# SparkBase.net
KiCad netlist of a schematic drawn in EAGLE
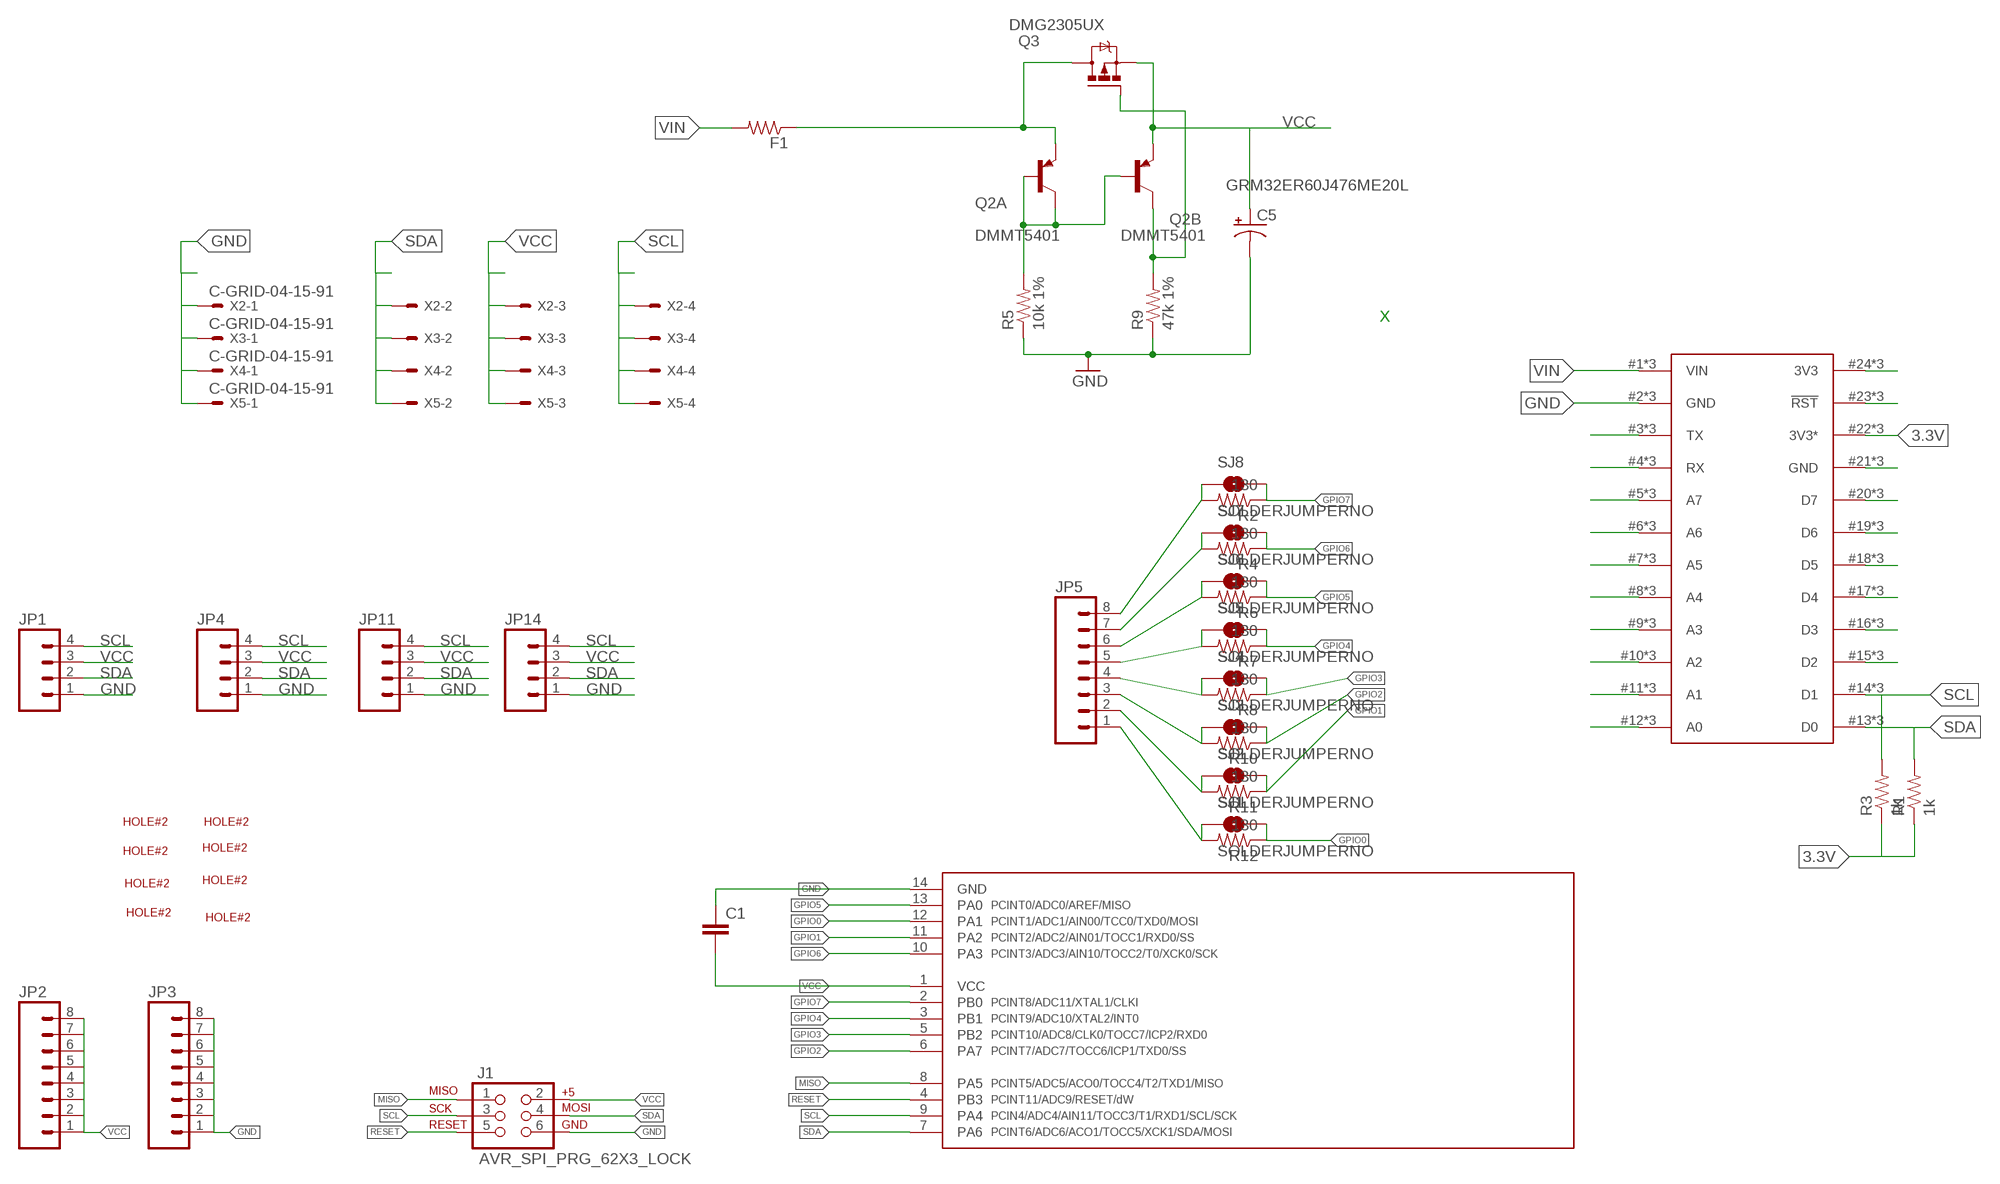
[diagram p0: schematic, sheet 1]

(export (version "E")
  (design (tool "Eeschema 10.0.6"))
  (components
    (comp (ref "C1")
      (value "CAP0805")
      (footprint "eagle-import:0805")
      (libsource (lib "eagle-import") (part "CAP0805"))
    )
    (comp (ref "C5")
      (value "CAP_POLC")
      (footprint "eagle-import:PANASONIC_C")
      (libsource (lib "eagle-import") (part "CAP_POLC"))
    )
    (comp (ref "F1")
      (value "RESISTOR0805-RES")
      (footprint "eagle-import:0805")
      (libsource (lib "eagle-import") (part "RESISTOR0805-RES"))
    )
    (comp (ref "J1")
      (value "AVR_SPI_PRG_62X3_LOCK")
      (footprint "eagle-import:2X3_LOCK")
      (libsource (lib "eagle-import") (part "AVR_SPI_PRG_62X3_LOCK"))
    )
    (comp (ref "JP1")
      (value "M04LOCK")
      (footprint "eagle-import:1X04_LOCK")
      (libsource (lib "eagle-import") (part "M04LOCK"))
    )
    (comp (ref "JP2")
      (value "M08NO_SILK")
      (footprint "eagle-import:1X08_NO_SILK")
      (libsource (lib "eagle-import") (part "M08NO_SILK"))
    )
    (comp (ref "JP3")
      (value "M08NO_SILK")
      (footprint "eagle-import:1X08_NO_SILK")
      (libsource (lib "eagle-import") (part "M08NO_SILK"))
    )
    (comp (ref "JP4")
      (value "M04LOCK")
      (footprint "eagle-import:1X04_LOCK")
      (libsource (lib "eagle-import") (part "M04LOCK"))
    )
    (comp (ref "JP5")
      (value "M08NO_SILK")
      (footprint "eagle-import:1X08_NO_SILK")
      (libsource (lib "eagle-import") (part "M08NO_SILK"))
    )
    (comp (ref "JP11")
      (value "M04LOCK")
      (footprint "eagle-import:1X04_LOCK")
      (libsource (lib "eagle-import") (part "M04LOCK"))
    )
    (comp (ref "JP14")
      (value "M04LOCK")
      (footprint "eagle-import:1X04_LOCK")
      (libsource (lib "eagle-import") (part "M04LOCK"))
    )
    (comp (ref "Q2")
      (value "DMMT5401")
      (footprint "eagle-import:SOT-26")
      (libsource (lib "eagle-import") (part "TRANSISTOR-DUAL-PNP"))
    )
    (comp (ref "Q3")
      (value "DMG2305UX")
      (footprint "eagle-import:MICRO3")
      (libsource (lib "eagle-import") (part "IRLML5203"))
    )
    (comp (ref "R1")
      (value "1k")
      (footprint "eagle-import:0805")
      (libsource (lib "eagle-import") (part "RESISTOR0805-RES"))
    )
    (comp (ref "R2")
      (value "130")
      (footprint "eagle-import:0805")
      (libsource (lib "eagle-import") (part "RESISTOR0805-RES"))
    )
    (comp (ref "R3")
      (value "1k")
      (footprint "eagle-import:0805")
      (libsource (lib "eagle-import") (part "RESISTOR0805-RES"))
    )
    (comp (ref "R4")
      (value "130")
      (footprint "eagle-import:0805")
      (libsource (lib "eagle-import") (part "RESISTOR0805-RES"))
    )
    (comp (ref "R5")
      (value "10k 1%")
      (footprint "eagle-import:0805")
      (libsource (lib "eagle-import") (part "RESISTOR0805-RES"))
    )
    (comp (ref "R6")
      (value "130")
      (footprint "eagle-import:0805")
      (libsource (lib "eagle-import") (part "RESISTOR0805-RES"))
    )
    (comp (ref "R7")
      (value "130")
      (footprint "eagle-import:0805")
      (libsource (lib "eagle-import") (part "RESISTOR0805-RES"))
    )
    (comp (ref "R8")
      (value "130")
      (footprint "eagle-import:0805")
      (libsource (lib "eagle-import") (part "RESISTOR0805-RES"))
    )
    (comp (ref "R9")
      (value "47k 1%")
      (footprint "eagle-import:0805")
      (libsource (lib "eagle-import") (part "RESISTOR0805-RES"))
    )
    (comp (ref "R10")
      (value "130")
      (footprint "eagle-import:0805")
      (libsource (lib "eagle-import") (part "RESISTOR0805-RES"))
    )
    (comp (ref "R11")
      (value "130")
      (footprint "eagle-import:0805")
      (libsource (lib "eagle-import") (part "RESISTOR0805-RES"))
    )
    (comp (ref "R12")
      (value "130")
      (footprint "eagle-import:0805")
      (libsource (lib "eagle-import") (part "RESISTOR0805-RES"))
    )
    (comp (ref "SJ1")
      (value "SOLDERJUMPERNO")
      (footprint "eagle-import:SJ_2S-NO")
      (libsource (lib "eagle-import") (part "SOLDERJUMPERNO"))
    )
    (comp (ref "SJ2")
      (value "SOLDERJUMPERNO")
      (footprint "eagle-import:SJ_2S-NO")
      (libsource (lib "eagle-import") (part "SOLDERJUMPERNO"))
    )
    (comp (ref "SJ3")
      (value "SOLDERJUMPERNO")
      (footprint "eagle-import:SJ_2S-NO")
      (libsource (lib "eagle-import") (part "SOLDERJUMPERNO"))
    )
    (comp (ref "SJ4")
      (value "SOLDERJUMPERNO")
      (footprint "eagle-import:SJ_2S-NO")
      (libsource (lib "eagle-import") (part "SOLDERJUMPERNO"))
    )
    (comp (ref "SJ5")
      (value "SOLDERJUMPERNO")
      (footprint "eagle-import:SJ_2S-NO")
      (libsource (lib "eagle-import") (part "SOLDERJUMPERNO"))
    )
    (comp (ref "SJ6")
      (value "SOLDERJUMPERNO")
      (footprint "eagle-import:SJ_2S-NO")
      (libsource (lib "eagle-import") (part "SOLDERJUMPERNO"))
    )
    (comp (ref "SJ7")
      (value "SOLDERJUMPERNO")
      (footprint "eagle-import:SJ_2S-NO")
      (libsource (lib "eagle-import") (part "SOLDERJUMPERNO"))
    )
    (comp (ref "SJ8")
      (value "SOLDERJUMPERNO")
      (footprint "eagle-import:SJ_2S-NO")
      (libsource (lib "eagle-import") (part "SOLDERJUMPERNO"))
    )
    (comp (ref "U$2")
      (value "SPARK_CORE")
      (footprint "eagle-import:SPARK_CORE_STACKABLE")
      (libsource (lib "eagle-import") (part "SPARK_CORE"))
    )
    (comp (ref "U$6")
      (value "TINY841")
      (footprint "eagle-import:SOIC14")
      (libsource (lib "eagle-import") (part "TINY841"))
    )
    (comp (ref "U$7")
      (value "HOLE#2")
      (footprint "eagle-import:HOLE-#2")
      (libsource (lib "eagle-import") (part "HOLE#2"))
    )
    (comp (ref "U$8")
      (value "HOLE#2")
      (footprint "eagle-import:HOLE-#2")
      (libsource (lib "eagle-import") (part "HOLE#2"))
    )
    (comp (ref "U$9")
      (value "HOLE#2")
      (footprint "eagle-import:HOLE-#2")
      (libsource (lib "eagle-import") (part "HOLE#2"))
    )
    (comp (ref "U$10")
      (value "HOLE#2")
      (footprint "eagle-import:HOLE-#2")
      (libsource (lib "eagle-import") (part "HOLE#2"))
    )
    (comp (ref "U$11")
      (value "HOLE#2")
      (footprint "eagle-import:HOLE-#2")
      (libsource (lib "eagle-import") (part "HOLE#2"))
    )
    (comp (ref "U$12")
      (value "HOLE#2")
      (footprint "eagle-import:HOLE-#2")
      (libsource (lib "eagle-import") (part "HOLE#2"))
    )
    (comp (ref "U$13")
      (value "HOLE#2")
      (footprint "eagle-import:HOLE-#2")
      (libsource (lib "eagle-import") (part "HOLE#2"))
    )
    (comp (ref "U$14")
      (value "HOLE#2")
      (footprint "eagle-import:HOLE-#2")
      (libsource (lib "eagle-import") (part "HOLE#2"))
    )
    (comp (ref "X2")
      (value "C-GRID-04-15-91")
      (footprint "eagle-import:15-91-04")
      (libsource (lib "eagle-import") (part "C-GRID-04-15-91"))
    )
    (comp (ref "X3")
      (value "C-GRID-04-15-91")
      (footprint "eagle-import:15-91-04")
      (libsource (lib "eagle-import") (part "C-GRID-04-15-91"))
    )
    (comp (ref "X4")
      (value "C-GRID-04-15-91")
      (footprint "eagle-import:15-91-04")
      (libsource (lib "eagle-import") (part "C-GRID-04-15-91"))
    )
    (comp (ref "X5")
      (value "C-GRID-04-15-91")
      (footprint "eagle-import:15-91-04")
      (libsource (lib "eagle-import") (part "C-GRID-04-15-91"))
    )
  )
  (nets
    (net (code "1") (name "3.3V") (class "Default")
      (node (ref "R1") (pin "1") (pinfunction "1_1") (pintype "passive"))
      (node (ref "R3") (pin "1") (pinfunction "1_1") (pintype "passive"))
      (node (ref "U$2") (pin "#22") (pinfunction "3V3*_#22") (pintype "power_in"))
      (node (ref "U$2") (pin "22") (pinfunction "3V3*_22") (pintype "power_in"))
      (node (ref "U$2") (pin "@22") (pinfunction "3V3*_@22") (pintype "power_in"))
    )
    (net (code "2") (name "GND") (class "Default")
      (node (ref "C1") (pin "1") (pinfunction "1_1") (pintype "passive"))
      (node (ref "C5") (pin "-") (pinfunction "-_-") (pintype "passive"))
      (node (ref "J1") (pin "6") (pinfunction "6_6") (pintype "passive"))
      (node (ref "JP1") (pin "1") (pinfunction "1_1") (pintype "passive"))
      (node (ref "JP11") (pin "1") (pinfunction "1_1") (pintype "passive"))
      (node (ref "JP14") (pin "1") (pinfunction "1_1") (pintype "passive"))
      (node (ref "JP3") (pin "1") (pinfunction "1_1") (pintype "passive"))
      (node (ref "JP3") (pin "2") (pinfunction "2_2") (pintype "passive"))
      (node (ref "JP3") (pin "3") (pinfunction "3_3") (pintype "passive"))
      (node (ref "JP3") (pin "4") (pinfunction "4_4") (pintype "passive"))
      (node (ref "JP3") (pin "5") (pinfunction "5_5") (pintype "passive"))
      (node (ref "JP3") (pin "6") (pinfunction "6_6") (pintype "passive"))
      (node (ref "JP3") (pin "7") (pinfunction "7_7") (pintype "passive"))
      (node (ref "JP3") (pin "8") (pinfunction "8_8") (pintype "passive"))
      (node (ref "JP4") (pin "1") (pinfunction "1_1") (pintype "passive"))
      (node (ref "R5") (pin "1") (pinfunction "1_1") (pintype "passive"))
      (node (ref "R9") (pin "1") (pinfunction "1_1") (pintype "passive"))
      (node (ref "U$2") (pin "#2") (pinfunction "GND_#2") (pintype "power_in"))
      (node (ref "U$2") (pin "2") (pinfunction "GND_2") (pintype "power_in"))
      (node (ref "U$2") (pin "@2") (pinfunction "GND_@2") (pintype "power_in"))
      (node (ref "U$6") (pin "14") (pinfunction "GND_14") (pintype "bidirectional"))
      (node (ref "X2") (pin "1") (pinfunction "S_1") (pintype "passive"))
      (node (ref "X3") (pin "1") (pinfunction "S_1") (pintype "passive"))
      (node (ref "X4") (pin "1") (pinfunction "S_1") (pintype "passive"))
      (node (ref "X5") (pin "1") (pinfunction "S_1") (pintype "passive"))
    )
    (net (code "3") (name "GPIO0") (class "Default")
      (node (ref "R12") (pin "1") (pinfunction "1_1") (pintype "passive"))
      (node (ref "SJ1") (pin "2") (pinfunction "2_2") (pintype "passive"))
      (node (ref "U$6") (pin "12") (pinfunction "PA1_12") (pintype "bidirectional"))
    )
    (net (code "4") (name "GPIO1") (class "Default")
      (node (ref "R11") (pin "1") (pinfunction "1_1") (pintype "passive"))
      (node (ref "SJ2") (pin "2") (pinfunction "2_2") (pintype "passive"))
      (node (ref "U$6") (pin "11") (pinfunction "PA2_11") (pintype "bidirectional"))
    )
    (net (code "5") (name "GPIO2") (class "Default")
      (node (ref "R10") (pin "1") (pinfunction "1_1") (pintype "passive"))
      (node (ref "SJ3") (pin "2") (pinfunction "2_2") (pintype "passive"))
      (node (ref "U$6") (pin "6") (pinfunction "PA7_6") (pintype "bidirectional"))
    )
    (net (code "6") (name "GPIO3") (class "Default")
      (node (ref "R8") (pin "1") (pinfunction "1_1") (pintype "passive"))
      (node (ref "SJ4") (pin "2") (pinfunction "2_2") (pintype "passive"))
      (node (ref "U$6") (pin "5") (pinfunction "PB2_5") (pintype "bidirectional"))
    )
    (net (code "7") (name "GPIO4") (class "Default")
      (node (ref "R7") (pin "1") (pinfunction "1_1") (pintype "passive"))
      (node (ref "SJ5") (pin "2") (pinfunction "2_2") (pintype "passive"))
      (node (ref "U$6") (pin "3") (pinfunction "PB1_3") (pintype "bidirectional"))
    )
    (net (code "8") (name "GPIO5") (class "Default")
      (node (ref "R6") (pin "1") (pinfunction "1_1") (pintype "passive"))
      (node (ref "SJ6") (pin "2") (pinfunction "2_2") (pintype "passive"))
      (node (ref "U$6") (pin "13") (pinfunction "PA0_13") (pintype "bidirectional"))
    )
    (net (code "9") (name "GPIO6") (class "Default")
      (node (ref "R4") (pin "1") (pinfunction "1_1") (pintype "passive"))
      (node (ref "SJ7") (pin "2") (pinfunction "2_2") (pintype "passive"))
      (node (ref "U$6") (pin "10") (pinfunction "PA3_10") (pintype "bidirectional"))
    )
    (net (code "10") (name "GPIO7") (class "Default")
      (node (ref "R2") (pin "1") (pinfunction "1_1") (pintype "passive"))
      (node (ref "SJ8") (pin "2") (pinfunction "2_2") (pintype "passive"))
      (node (ref "U$6") (pin "2") (pinfunction "PB0_2") (pintype "bidirectional"))
    )
    (net (code "11") (name "MISO") (class "Default")
      (node (ref "J1") (pin "1") (pinfunction "1_1") (pintype "passive"))
      (node (ref "U$6") (pin "8") (pinfunction "PA5_8") (pintype "bidirectional"))
    )
    (net (code "12") (name "Net-(JP5-Pad1)") (class "Default")
      (node (ref "JP5") (pin "1") (pinfunction "1_1") (pintype "passive"))
      (node (ref "R12") (pin "2") (pinfunction "2_2") (pintype "passive"))
      (node (ref "SJ1") (pin "1") (pinfunction "1_1") (pintype "passive"))
    )
    (net (code "13") (name "Net-(JP5-Pad2)") (class "Default")
      (node (ref "JP5") (pin "2") (pinfunction "2_2") (pintype "passive"))
      (node (ref "R11") (pin "2") (pinfunction "2_2") (pintype "passive"))
      (node (ref "SJ2") (pin "1") (pinfunction "1_1") (pintype "passive"))
    )
    (net (code "14") (name "Net-(JP5-Pad3)") (class "Default")
      (node (ref "JP5") (pin "3") (pinfunction "3_3") (pintype "passive"))
      (node (ref "R10") (pin "2") (pinfunction "2_2") (pintype "passive"))
      (node (ref "SJ3") (pin "1") (pinfunction "1_1") (pintype "passive"))
    )
    (net (code "15") (name "Net-(JP5-Pad4)") (class "Default")
      (node (ref "JP5") (pin "4") (pinfunction "4_4") (pintype "passive"))
      (node (ref "R8") (pin "2") (pinfunction "2_2") (pintype "passive"))
      (node (ref "SJ4") (pin "1") (pinfunction "1_1") (pintype "passive"))
    )
    (net (code "16") (name "Net-(JP5-Pad5)") (class "Default")
      (node (ref "JP5") (pin "5") (pinfunction "5_5") (pintype "passive"))
      (node (ref "R7") (pin "2") (pinfunction "2_2") (pintype "passive"))
      (node (ref "SJ5") (pin "1") (pinfunction "1_1") (pintype "passive"))
    )
    (net (code "17") (name "Net-(JP5-Pad6)") (class "Default")
      (node (ref "JP5") (pin "6") (pinfunction "6_6") (pintype "passive"))
      (node (ref "R6") (pin "2") (pinfunction "2_2") (pintype "passive"))
      (node (ref "SJ6") (pin "1") (pinfunction "1_1") (pintype "passive"))
    )
    (net (code "18") (name "Net-(JP5-Pad7)") (class "Default")
      (node (ref "JP5") (pin "7") (pinfunction "7_7") (pintype "passive"))
      (node (ref "R4") (pin "2") (pinfunction "2_2") (pintype "passive"))
      (node (ref "SJ7") (pin "1") (pinfunction "1_1") (pintype "passive"))
    )
    (net (code "19") (name "Net-(JP5-Pad8)") (class "Default")
      (node (ref "JP5") (pin "8") (pinfunction "8_8") (pintype "passive"))
      (node (ref "R2") (pin "2") (pinfunction "2_2") (pintype "passive"))
      (node (ref "SJ8") (pin "1") (pinfunction "1_1") (pintype "passive"))
    )
    (net (code "20") (name "Net-(Q2A-B)") (class "Default")
      (node (ref "Q2") (pin "1") (pinfunction "C_1") (pintype "passive"))
      (node (ref "Q2") (pin "2") (pinfunction "B_2") (pintype "passive"))
      (node (ref "Q2") (pin "3") (pinfunction "B_3") (pintype "passive"))
      (node (ref "R5") (pin "2") (pinfunction "2_2") (pintype "passive"))
    )
    (net (code "21") (name "Net-(Q2A-E)") (class "Default")
      (node (ref "F1") (pin "1") (pinfunction "1_1") (pintype "passive"))
      (node (ref "Q2") (pin "6") (pinfunction "E_6") (pintype "passive"))
      (node (ref "Q3") (pin "3") (pinfunction "D_3") (pintype "passive"))
    )
    (net (code "22") (name "Net-(Q2B-C)") (class "Default")
      (node (ref "Q2") (pin "4") (pinfunction "C_4") (pintype "passive"))
      (node (ref "Q3") (pin "1") (pinfunction "G_1") (pintype "passive"))
      (node (ref "R9") (pin "2") (pinfunction "2_2") (pintype "passive"))
    )
    (net (code "23") (name "Net-(U$2-3V3-Pad#24)") (class "Default")
      (node (ref "U$2") (pin "#24") (pinfunction "3V3_#24") (pintype "power_in"))
      (node (ref "U$2") (pin "24") (pinfunction "3V3_24") (pintype "power_in"))
      (node (ref "U$2") (pin "@24") (pinfunction "3V3_@24") (pintype "power_in"))
    )
    (net (code "24") (name "Net-(U$2-A0-Pad#12)") (class "Default")
      (node (ref "U$2") (pin "#12") (pinfunction "A0_#12") (pintype "bidirectional"))
      (node (ref "U$2") (pin "12") (pinfunction "A0_12") (pintype "bidirectional"))
      (node (ref "U$2") (pin "@12") (pinfunction "A0_@12") (pintype "bidirectional"))
    )
    (net (code "25") (name "Net-(U$2-A1-Pad#11)") (class "Default")
      (node (ref "U$2") (pin "#11") (pinfunction "A1_#11") (pintype "bidirectional"))
      (node (ref "U$2") (pin "11") (pinfunction "A1_11") (pintype "bidirectional"))
      (node (ref "U$2") (pin "@11") (pinfunction "A1_@11") (pintype "bidirectional"))
    )
    (net (code "26") (name "Net-(U$2-A2-Pad#10)") (class "Default")
      (node (ref "U$2") (pin "#10") (pinfunction "A2_#10") (pintype "bidirectional"))
      (node (ref "U$2") (pin "10") (pinfunction "A2_10") (pintype "bidirectional"))
      (node (ref "U$2") (pin "@10") (pinfunction "A2_@10") (pintype "bidirectional"))
    )
    (net (code "27") (name "Net-(U$2-A3-Pad#9)") (class "Default")
      (node (ref "U$2") (pin "#9") (pinfunction "A3_#9") (pintype "bidirectional"))
      (node (ref "U$2") (pin "9") (pinfunction "A3_9") (pintype "bidirectional"))
      (node (ref "U$2") (pin "@9") (pinfunction "A3_@9") (pintype "bidirectional"))
    )
    (net (code "28") (name "Net-(U$2-A4-Pad#8)") (class "Default")
      (node (ref "U$2") (pin "#8") (pinfunction "A4_#8") (pintype "bidirectional"))
      (node (ref "U$2") (pin "8") (pinfunction "A4_8") (pintype "bidirectional"))
      (node (ref "U$2") (pin "@8") (pinfunction "A4_@8") (pintype "bidirectional"))
    )
    (net (code "29") (name "Net-(U$2-A5-Pad#7)") (class "Default")
      (node (ref "U$2") (pin "#7") (pinfunction "A5_#7") (pintype "bidirectional"))
      (node (ref "U$2") (pin "7") (pinfunction "A5_7") (pintype "bidirectional"))
      (node (ref "U$2") (pin "@7") (pinfunction "A5_@7") (pintype "bidirectional"))
    )
    (net (code "30") (name "Net-(U$2-A6-Pad#6)") (class "Default")
      (node (ref "U$2") (pin "#6") (pinfunction "A6_#6") (pintype "bidirectional"))
      (node (ref "U$2") (pin "6") (pinfunction "A6_6") (pintype "bidirectional"))
      (node (ref "U$2") (pin "@6") (pinfunction "A6_@6") (pintype "bidirectional"))
    )
    (net (code "31") (name "Net-(U$2-A7-Pad#5)") (class "Default")
      (node (ref "U$2") (pin "#5") (pinfunction "A7_#5") (pintype "bidirectional"))
      (node (ref "U$2") (pin "5") (pinfunction "A7_5") (pintype "bidirectional"))
      (node (ref "U$2") (pin "@5") (pinfunction "A7_@5") (pintype "bidirectional"))
    )
    (net (code "32") (name "Net-(U$2-D2-Pad#15)") (class "Default")
      (node (ref "U$2") (pin "#15") (pinfunction "D2_#15") (pintype "bidirectional"))
      (node (ref "U$2") (pin "15") (pinfunction "D2_15") (pintype "bidirectional"))
      (node (ref "U$2") (pin "@15") (pinfunction "D2_@15") (pintype "bidirectional"))
    )
    (net (code "33") (name "Net-(U$2-D3-Pad#16)") (class "Default")
      (node (ref "U$2") (pin "#16") (pinfunction "D3_#16") (pintype "bidirectional"))
      (node (ref "U$2") (pin "16") (pinfunction "D3_16") (pintype "bidirectional"))
      (node (ref "U$2") (pin "@16") (pinfunction "D3_@16") (pintype "bidirectional"))
    )
    (net (code "34") (name "Net-(U$2-D4-Pad#17)") (class "Default")
      (node (ref "U$2") (pin "#17") (pinfunction "D4_#17") (pintype "bidirectional"))
      (node (ref "U$2") (pin "17") (pinfunction "D4_17") (pintype "bidirectional"))
      (node (ref "U$2") (pin "@17") (pinfunction "D4_@17") (pintype "bidirectional"))
    )
    (net (code "35") (name "Net-(U$2-D5-Pad#18)") (class "Default")
      (node (ref "U$2") (pin "#18") (pinfunction "D5_#18") (pintype "bidirectional"))
      (node (ref "U$2") (pin "18") (pinfunction "D5_18") (pintype "bidirectional"))
      (node (ref "U$2") (pin "@18") (pinfunction "D5_@18") (pintype "bidirectional"))
    )
    (net (code "36") (name "Net-(U$2-D6-Pad#19)") (class "Default")
      (node (ref "U$2") (pin "#19") (pinfunction "D6_#19") (pintype "bidirectional"))
      (node (ref "U$2") (pin "19") (pinfunction "D6_19") (pintype "bidirectional"))
      (node (ref "U$2") (pin "@19") (pinfunction "D6_@19") (pintype "bidirectional"))
    )
    (net (code "37") (name "Net-(U$2-D7-Pad#20)") (class "Default")
      (node (ref "U$2") (pin "#20") (pinfunction "D7_#20") (pintype "bidirectional"))
      (node (ref "U$2") (pin "20") (pinfunction "D7_20") (pintype "bidirectional"))
      (node (ref "U$2") (pin "@20") (pinfunction "D7_@20") (pintype "bidirectional"))
    )
    (net (code "38") (name "Net-(U$2-GND-Pad#21)") (class "Default")
      (node (ref "U$2") (pin "#21") (pinfunction "GND_#21") (pintype "power_in"))
      (node (ref "U$2") (pin "21") (pinfunction "GND_21") (pintype "power_in"))
      (node (ref "U$2") (pin "@21") (pinfunction "GND_@21") (pintype "power_in"))
    )
    (net (code "39") (name "Net-(U$2-RX-Pad#4)") (class "Default")
      (node (ref "U$2") (pin "#4") (pinfunction "RX_#4") (pintype "bidirectional"))
      (node (ref "U$2") (pin "4") (pinfunction "RX_4") (pintype "bidirectional"))
      (node (ref "U$2") (pin "@4") (pinfunction "RX_@4") (pintype "bidirectional"))
    )
    (net (code "40") (name "Net-(U$2-TX-Pad#3)") (class "Default")
      (node (ref "U$2") (pin "#3") (pinfunction "TX_#3") (pintype "bidirectional"))
      (node (ref "U$2") (pin "3") (pinfunction "TX_3") (pintype "bidirectional"))
      (node (ref "U$2") (pin "@3") (pinfunction "TX_@3") (pintype "bidirectional"))
    )
    (net (code "41") (name "Net-(U$2-~{RST}-Pad#23)") (class "Default")
      (node (ref "U$2") (pin "#23") (pinfunction "~{RST}_#23") (pintype "bidirectional"))
      (node (ref "U$2") (pin "23") (pinfunction "~{RST}_23") (pintype "bidirectional"))
      (node (ref "U$2") (pin "@23") (pinfunction "~{RST}_@23") (pintype "bidirectional"))
    )
    (net (code "42") (name "RESET") (class "Default")
      (node (ref "J1") (pin "5") (pinfunction "5_5") (pintype "passive"))
      (node (ref "U$6") (pin "4") (pinfunction "PB3_4") (pintype "bidirectional"))
    )
    (net (code "43") (name "SCL") (class "Default")
      (node (ref "J1") (pin "3") (pinfunction "3_3") (pintype "passive"))
      (node (ref "JP1") (pin "4") (pinfunction "4_4") (pintype "passive"))
      (node (ref "JP11") (pin "4") (pinfunction "4_4") (pintype "passive"))
      (node (ref "JP14") (pin "4") (pinfunction "4_4") (pintype "passive"))
      (node (ref "JP4") (pin "4") (pinfunction "4_4") (pintype "passive"))
      (node (ref "R3") (pin "2") (pinfunction "2_2") (pintype "passive"))
      (node (ref "U$2") (pin "#14") (pinfunction "D1_#14") (pintype "bidirectional"))
      (node (ref "U$2") (pin "14") (pinfunction "D1_14") (pintype "bidirectional"))
      (node (ref "U$2") (pin "@14") (pinfunction "D1_@14") (pintype "bidirectional"))
      (node (ref "U$6") (pin "9") (pinfunction "PA4_9") (pintype "bidirectional"))
      (node (ref "X2") (pin "4") (pinfunction "S_4") (pintype "passive"))
      (node (ref "X3") (pin "4") (pinfunction "S_4") (pintype "passive"))
      (node (ref "X4") (pin "4") (pinfunction "S_4") (pintype "passive"))
      (node (ref "X5") (pin "4") (pinfunction "S_4") (pintype "passive"))
    )
    (net (code "44") (name "SDA") (class "Default")
      (node (ref "J1") (pin "4") (pinfunction "4_4") (pintype "passive"))
      (node (ref "JP1") (pin "2") (pinfunction "2_2") (pintype "passive"))
      (node (ref "JP11") (pin "2") (pinfunction "2_2") (pintype "passive"))
      (node (ref "JP14") (pin "2") (pinfunction "2_2") (pintype "passive"))
      (node (ref "JP4") (pin "2") (pinfunction "2_2") (pintype "passive"))
      (node (ref "R1") (pin "2") (pinfunction "2_2") (pintype "passive"))
      (node (ref "U$2") (pin "#13") (pinfunction "D0_#13") (pintype "bidirectional"))
      (node (ref "U$2") (pin "13") (pinfunction "D0_13") (pintype "bidirectional"))
      (node (ref "U$2") (pin "@13") (pinfunction "D0_@13") (pintype "bidirectional"))
      (node (ref "U$6") (pin "7") (pinfunction "PA6_7") (pintype "bidirectional"))
      (node (ref "X2") (pin "2") (pinfunction "S_2") (pintype "passive"))
      (node (ref "X3") (pin "2") (pinfunction "S_2") (pintype "passive"))
      (node (ref "X4") (pin "2") (pinfunction "S_2") (pintype "passive"))
      (node (ref "X5") (pin "2") (pinfunction "S_2") (pintype "passive"))
    )
    (net (code "45") (name "VCC") (class "Default")
      (node (ref "C1") (pin "2") (pinfunction "2_2") (pintype "passive"))
      (node (ref "C5") (pin "+") (pinfunction "+_+") (pintype "passive"))
      (node (ref "J1") (pin "2") (pinfunction "2_2") (pintype "passive"))
      (node (ref "JP1") (pin "3") (pinfunction "3_3") (pintype "passive"))
      (node (ref "JP11") (pin "3") (pinfunction "3_3") (pintype "passive"))
      (node (ref "JP14") (pin "3") (pinfunction "3_3") (pintype "passive"))
      (node (ref "JP2") (pin "1") (pinfunction "1_1") (pintype "passive"))
      (node (ref "JP2") (pin "2") (pinfunction "2_2") (pintype "passive"))
      (node (ref "JP2") (pin "3") (pinfunction "3_3") (pintype "passive"))
      (node (ref "JP2") (pin "4") (pinfunction "4_4") (pintype "passive"))
      (node (ref "JP2") (pin "5") (pinfunction "5_5") (pintype "passive"))
      (node (ref "JP2") (pin "6") (pinfunction "6_6") (pintype "passive"))
      (node (ref "JP2") (pin "7") (pinfunction "7_7") (pintype "passive"))
      (node (ref "JP2") (pin "8") (pinfunction "8_8") (pintype "passive"))
      (node (ref "JP4") (pin "3") (pinfunction "3_3") (pintype "passive"))
      (node (ref "Q2") (pin "5") (pinfunction "E_5") (pintype "passive"))
      (node (ref "Q3") (pin "2") (pinfunction "S_2") (pintype "passive"))
      (node (ref "U$6") (pin "1") (pinfunction "VCC_1") (pintype "bidirectional"))
      (node (ref "X2") (pin "3") (pinfunction "S_3") (pintype "passive"))
      (node (ref "X3") (pin "3") (pinfunction "S_3") (pintype "passive"))
      (node (ref "X4") (pin "3") (pinfunction "S_3") (pintype "passive"))
      (node (ref "X5") (pin "3") (pinfunction "S_3") (pintype "passive"))
    )
    (net (code "46") (name "VIN") (class "Default")
      (node (ref "F1") (pin "2") (pinfunction "2_2") (pintype "passive"))
      (node (ref "U$2") (pin "#1") (pinfunction "VIN_#1") (pintype "power_in"))
      (node (ref "U$2") (pin "1") (pinfunction "VIN_1") (pintype "power_in"))
      (node (ref "U$2") (pin "@1") (pinfunction "VIN_@1") (pintype "power_in"))
    )
    (net (code "47") (name "unconnected-(U$7-HOLE-PadP$1)") (class "Default")
      (node (ref "U$7") (pin "P$1") (pinfunction "HOLE_P$1") (pintype "bidirectional"))
    )
    (net (code "48") (name "unconnected-(U$8-HOLE-PadP$1)") (class "Default")
      (node (ref "U$8") (pin "P$1") (pinfunction "HOLE_P$1") (pintype "bidirectional"))
    )
    (net (code "49") (name "unconnected-(U$9-HOLE-PadP$1)") (class "Default")
      (node (ref "U$9") (pin "P$1") (pinfunction "HOLE_P$1") (pintype "bidirectional"))
    )
    (net (code "50") (name "unconnected-(U$10-HOLE-PadP$1)") (class "Default")
      (node (ref "U$10") (pin "P$1") (pinfunction "HOLE_P$1") (pintype "bidirectional"))
    )
    (net (code "51") (name "unconnected-(U$11-HOLE-PadP$1)") (class "Default")
      (node (ref "U$11") (pin "P$1") (pinfunction "HOLE_P$1") (pintype "bidirectional"))
    )
    (net (code "52") (name "unconnected-(U$12-HOLE-PadP$1)") (class "Default")
      (node (ref "U$12") (pin "P$1") (pinfunction "HOLE_P$1") (pintype "bidirectional"))
    )
    (net (code "53") (name "unconnected-(U$13-HOLE-PadP$1)") (class "Default")
      (node (ref "U$13") (pin "P$1") (pinfunction "HOLE_P$1") (pintype "bidirectional"))
    )
    (net (code "54") (name "unconnected-(U$14-HOLE-PadP$1)") (class "Default")
      (node (ref "U$14") (pin "P$1") (pinfunction "HOLE_P$1") (pintype "bidirectional"))
    )
  )
)
